# Tryckgivare.net
KiCad netlist of a schematic drawn in EAGLE
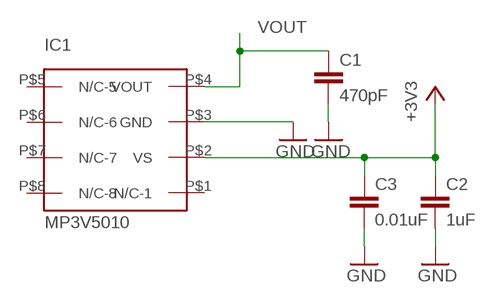
[diagram p0: schematic, sheet 1]

(export (version "E")
  (design (tool "Eeschema 10.0.6"))
  (components
    (comp (ref "C1")
      (value "470pF")
      (footprint "eagle-import:C0805")
      (libsource (lib "eagle-import") (part "C-EUC0805"))
    )
    (comp (ref "C2")
      (value "1uF")
      (footprint "eagle-import:C0805")
      (libsource (lib "eagle-import") (part "C-EUC0805"))
    )
    (comp (ref "C3")
      (value "0.01uF")
      (footprint "eagle-import:C0805")
      (libsource (lib "eagle-import") (part "C-EUC0805"))
    )
    (comp (ref "IC1")
      (value "MP3V5010")
      (footprint "eagle-import:CASE1351")
      (libsource (lib "eagle-import") (part "MP3V5010"))
    )
  )
  (nets
    (net (code "1") (name "+3V3") (class "Default")
      (node (ref "C2") (pin "1") (pinfunction "1_1") (pintype "passive"))
      (node (ref "C3") (pin "1") (pinfunction "1_1") (pintype "passive"))
      (node (ref "IC1") (pin "P$2") (pinfunction "VS_P$2") (pintype "bidirectional"))
    )
    (net (code "2") (name "/VOUT") (class "Default")
      (node (ref "C1") (pin "1") (pinfunction "1_1") (pintype "passive"))
      (node (ref "IC1") (pin "P$4") (pinfunction "VOUT_P$4") (pintype "bidirectional"))
    )
    (net (code "3") (name "GND") (class "Default")
      (node (ref "C1") (pin "2") (pinfunction "2_2") (pintype "passive"))
      (node (ref "C2") (pin "2") (pinfunction "2_2") (pintype "passive"))
      (node (ref "C3") (pin "2") (pinfunction "2_2") (pintype "passive"))
      (node (ref "IC1") (pin "P$3") (pinfunction "GND_P$3") (pintype "bidirectional"))
    )
    (net (code "4") (name "unconnected-(IC1-N{slash}C-1-PadP$1)") (class "Default")
      (node (ref "IC1") (pin "P$1") (pinfunction "N/C-1_P$1") (pintype "bidirectional"))
    )
    (net (code "5") (name "unconnected-(IC1-N{slash}C-5-PadP$5)") (class "Default")
      (node (ref "IC1") (pin "P$5") (pinfunction "N/C-5_P$5") (pintype "bidirectional"))
    )
    (net (code "6") (name "unconnected-(IC1-N{slash}C-6-PadP$6)") (class "Default")
      (node (ref "IC1") (pin "P$6") (pinfunction "N/C-6_P$6") (pintype "bidirectional"))
    )
    (net (code "7") (name "unconnected-(IC1-N{slash}C-7-PadP$7)") (class "Default")
      (node (ref "IC1") (pin "P$7") (pinfunction "N/C-7_P$7") (pintype "bidirectional"))
    )
    (net (code "8") (name "unconnected-(IC1-N{slash}C-8-PadP$8)") (class "Default")
      (node (ref "IC1") (pin "P$8") (pinfunction "N/C-8_P$8") (pintype "bidirectional"))
    )
  )
)
